# IR_7arry.net
KiCad netlist of a schematic drawn in Altium Designer
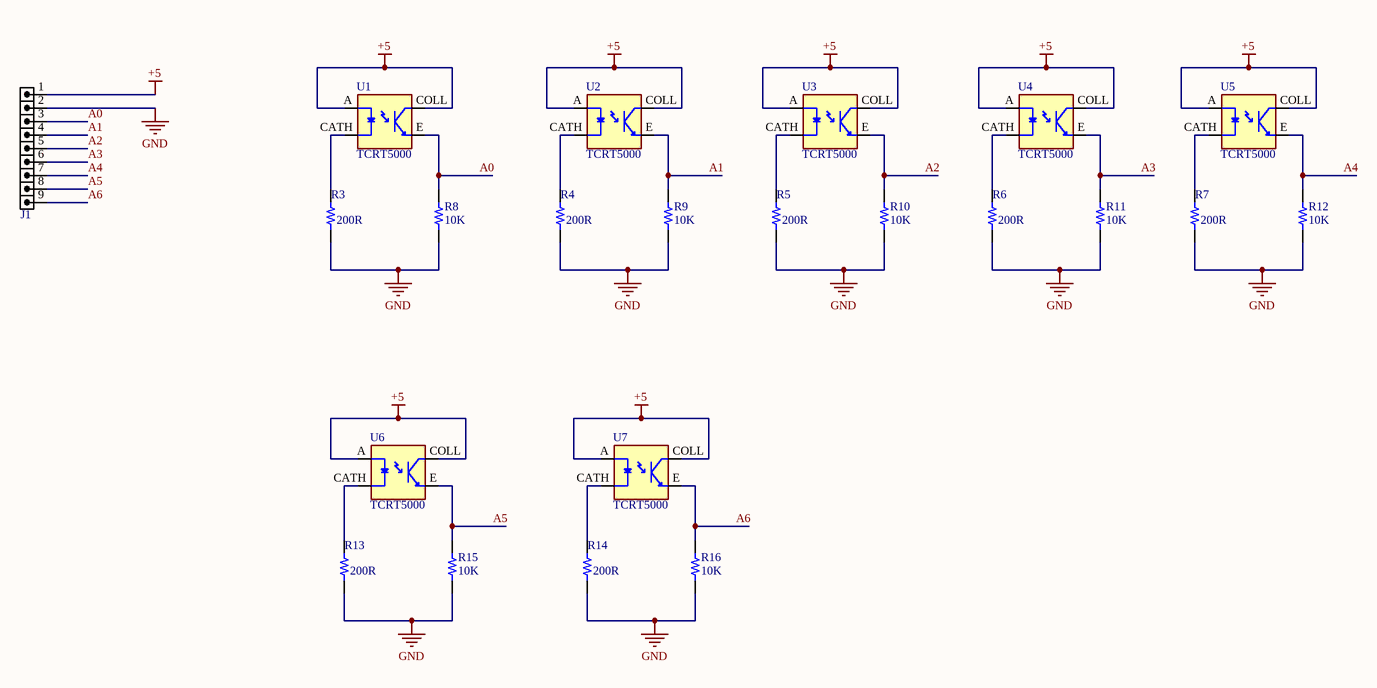
[diagram p0: IR_7arry.SchDoc]

(export (version "E")
  (design (tool "Eeschema 10.0.6"))
  (components
    (comp (ref "J1")
      (value "HDR1X9")
      (footprint "HDRR_M_1X9")
      (description "CONN, HEADER, RightAngle, Male, pitch: 2.54mm, 9POS")
      (libsource (lib "Conn Header") (part "HDRR_M_1X9"))
    )
    (comp (ref "R3")
      (value "200R")
      (footprint "RES TH 1/8W AXIAL-0.25")
      (description "TH Resistor")
      (libsource (lib "Resistor") (part "Res TH 1/8W AXIAL-0.25"))
    )
    (comp (ref "R4")
      (value "200R")
      (footprint "RES TH 1/8W AXIAL-0.25")
      (description "TH Resistor")
      (libsource (lib "Resistor") (part "Res TH 1/8W AXIAL-0.25"))
    )
    (comp (ref "R5")
      (value "200R")
      (footprint "RES TH 1/8W AXIAL-0.25")
      (description "TH Resistor")
      (libsource (lib "Resistor") (part "Res TH 1/8W AXIAL-0.25"))
    )
    (comp (ref "R6")
      (value "200R")
      (footprint "RES TH 1/8W AXIAL-0.25")
      (description "TH Resistor")
      (libsource (lib "Resistor") (part "Res TH 1/8W AXIAL-0.25"))
    )
    (comp (ref "R7")
      (value "200R")
      (footprint "RES TH 1/8W AXIAL-0.25")
      (description "TH Resistor")
      (libsource (lib "Resistor") (part "Res TH 1/8W AXIAL-0.25"))
    )
    (comp (ref "R8")
      (value "10K")
      (footprint "RES TH 1/8W AXIAL-0.25")
      (description "TH Resistor")
      (libsource (lib "Resistor") (part "Res TH 1/8W AXIAL-0.25"))
    )
    (comp (ref "R9")
      (value "10K")
      (footprint "RES TH 1/8W AXIAL-0.25")
      (description "TH Resistor")
      (libsource (lib "Resistor") (part "Res TH 1/8W AXIAL-0.25"))
    )
    (comp (ref "R10")
      (value "10K")
      (footprint "RES TH 1/8W AXIAL-0.25")
      (description "TH Resistor")
      (libsource (lib "Resistor") (part "Res TH 1/8W AXIAL-0.25"))
    )
    (comp (ref "R11")
      (value "10K")
      (footprint "RES TH 1/8W AXIAL-0.25")
      (description "TH Resistor")
      (libsource (lib "Resistor") (part "Res TH 1/8W AXIAL-0.25"))
    )
    (comp (ref "R12")
      (value "10K")
      (footprint "RES TH 1/8W AXIAL-0.25")
      (description "TH Resistor")
      (libsource (lib "Resistor") (part "Res TH 1/8W AXIAL-0.25"))
    )
    (comp (ref "R13")
      (value "200R")
      (footprint "RES TH 1/8W AXIAL-0.25")
      (description "TH Resistor")
      (libsource (lib "Resistor") (part "Res TH 1/8W AXIAL-0.25"))
    )
    (comp (ref "R14")
      (value "200R")
      (footprint "RES TH 1/8W AXIAL-0.25")
      (description "TH Resistor")
      (libsource (lib "Resistor") (part "Res TH 1/8W AXIAL-0.25"))
    )
    (comp (ref "R15")
      (value "10K")
      (footprint "RES TH 1/8W AXIAL-0.25")
      (description "TH Resistor")
      (libsource (lib "Resistor") (part "Res TH 1/8W AXIAL-0.25"))
    )
    (comp (ref "R16")
      (value "10K")
      (footprint "RES TH 1/8W AXIAL-0.25")
      (description "TH Resistor")
      (libsource (lib "Resistor") (part "Res TH 1/8W AXIAL-0.25"))
    )
    (comp (ref "U1")
      (value "TCRT5000")
      (footprint "OPTO_TCRT5000")
      (description "950 nm 60 mA Through Hole Reflective Optical Sensor with Transistor Output")
      (libsource (lib "TCRT5000") (part "TCRT5000"))
    )
    (comp (ref "U2")
      (value "TCRT5000")
      (footprint "OPTO_TCRT5000")
      (description "950 nm 60 mA Through Hole Reflective Optical Sensor with Transistor Output")
      (libsource (lib "TCRT5000") (part "TCRT5000"))
    )
    (comp (ref "U3")
      (value "TCRT5000")
      (footprint "OPTO_TCRT5000")
      (description "950 nm 60 mA Through Hole Reflective Optical Sensor with Transistor Output")
      (libsource (lib "TCRT5000") (part "TCRT5000"))
    )
    (comp (ref "U4")
      (value "TCRT5000")
      (footprint "OPTO_TCRT5000")
      (description "950 nm 60 mA Through Hole Reflective Optical Sensor with Transistor Output")
      (libsource (lib "TCRT5000") (part "TCRT5000"))
    )
    (comp (ref "U5")
      (value "TCRT5000")
      (footprint "OPTO_TCRT5000")
      (description "950 nm 60 mA Through Hole Reflective Optical Sensor with Transistor Output")
      (libsource (lib "TCRT5000") (part "TCRT5000"))
    )
    (comp (ref "U6")
      (value "TCRT5000")
      (footprint "OPTO_TCRT5000")
      (description "950 nm 60 mA Through Hole Reflective Optical Sensor with Transistor Output")
      (libsource (lib "TCRT5000") (part "TCRT5000"))
    )
    (comp (ref "U7")
      (value "TCRT5000")
      (footprint "OPTO_TCRT5000")
      (description "950 nm 60 mA Through Hole Reflective Optical Sensor with Transistor Output")
      (libsource (lib "TCRT5000") (part "TCRT5000"))
    )
  )
  (nets
    (net (code "1") (name "+5") (class "Default")
      (node (ref "J1") (pin "1") (pinfunction "1_1") (pintype "passive"))
      (node (ref "U1") (pin "A") (pinfunction "A_A") (pintype "passive"))
      (node (ref "U1") (pin "COLL") (pinfunction "COLL_COLL") (pintype "passive"))
      (node (ref "U2") (pin "A") (pinfunction "A_A") (pintype "passive"))
      (node (ref "U2") (pin "COLL") (pinfunction "COLL_COLL") (pintype "passive"))
      (node (ref "U3") (pin "A") (pinfunction "A_A") (pintype "passive"))
      (node (ref "U3") (pin "COLL") (pinfunction "COLL_COLL") (pintype "passive"))
      (node (ref "U4") (pin "A") (pinfunction "A_A") (pintype "passive"))
      (node (ref "U4") (pin "COLL") (pinfunction "COLL_COLL") (pintype "passive"))
      (node (ref "U5") (pin "A") (pinfunction "A_A") (pintype "passive"))
      (node (ref "U5") (pin "COLL") (pinfunction "COLL_COLL") (pintype "passive"))
      (node (ref "U6") (pin "A") (pinfunction "A_A") (pintype "passive"))
      (node (ref "U6") (pin "COLL") (pinfunction "COLL_COLL") (pintype "passive"))
      (node (ref "U7") (pin "A") (pinfunction "A_A") (pintype "passive"))
      (node (ref "U7") (pin "COLL") (pinfunction "COLL_COLL") (pintype "passive"))
    )
    (net (code "2") (name "/A0") (class "Default")
      (node (ref "J1") (pin "3") (pinfunction "3_3") (pintype "passive"))
      (node (ref "R8") (pin "2") (pinfunction "2_2") (pintype "passive"))
      (node (ref "U1") (pin "E") (pinfunction "E_E") (pintype "passive"))
    )
    (net (code "3") (name "/A1") (class "Default")
      (node (ref "J1") (pin "4") (pinfunction "4_4") (pintype "passive"))
      (node (ref "R9") (pin "2") (pinfunction "2_2") (pintype "passive"))
      (node (ref "U2") (pin "E") (pinfunction "E_E") (pintype "passive"))
    )
    (net (code "4") (name "/A2") (class "Default")
      (node (ref "J1") (pin "5") (pinfunction "5_5") (pintype "passive"))
      (node (ref "R10") (pin "2") (pinfunction "2_2") (pintype "passive"))
      (node (ref "U3") (pin "E") (pinfunction "E_E") (pintype "passive"))
    )
    (net (code "5") (name "/A3") (class "Default")
      (node (ref "J1") (pin "6") (pinfunction "6_6") (pintype "passive"))
      (node (ref "R11") (pin "2") (pinfunction "2_2") (pintype "passive"))
      (node (ref "U4") (pin "E") (pinfunction "E_E") (pintype "passive"))
    )
    (net (code "6") (name "/A4") (class "Default")
      (node (ref "J1") (pin "7") (pinfunction "7_7") (pintype "passive"))
      (node (ref "R12") (pin "2") (pinfunction "2_2") (pintype "passive"))
      (node (ref "U5") (pin "E") (pinfunction "E_E") (pintype "passive"))
    )
    (net (code "7") (name "/A5") (class "Default")
      (node (ref "J1") (pin "8") (pinfunction "8_8") (pintype "passive"))
      (node (ref "R15") (pin "2") (pinfunction "2_2") (pintype "passive"))
      (node (ref "U6") (pin "E") (pinfunction "E_E") (pintype "passive"))
    )
    (net (code "8") (name "/A6") (class "Default")
      (node (ref "J1") (pin "9") (pinfunction "9_9") (pintype "passive"))
      (node (ref "R16") (pin "2") (pinfunction "2_2") (pintype "passive"))
      (node (ref "U7") (pin "E") (pinfunction "E_E") (pintype "passive"))
    )
    (net (code "9") (name "GND") (class "Default")
      (node (ref "J1") (pin "2") (pinfunction "2_2") (pintype "passive"))
      (node (ref "R10") (pin "1") (pinfunction "1_1") (pintype "passive"))
      (node (ref "R11") (pin "1") (pinfunction "1_1") (pintype "passive"))
      (node (ref "R12") (pin "1") (pinfunction "1_1") (pintype "passive"))
      (node (ref "R13") (pin "1") (pinfunction "1_1") (pintype "passive"))
      (node (ref "R14") (pin "1") (pinfunction "1_1") (pintype "passive"))
      (node (ref "R15") (pin "1") (pinfunction "1_1") (pintype "passive"))
      (node (ref "R16") (pin "1") (pinfunction "1_1") (pintype "passive"))
      (node (ref "R3") (pin "1") (pinfunction "1_1") (pintype "passive"))
      (node (ref "R4") (pin "1") (pinfunction "1_1") (pintype "passive"))
      (node (ref "R5") (pin "1") (pinfunction "1_1") (pintype "passive"))
      (node (ref "R6") (pin "1") (pinfunction "1_1") (pintype "passive"))
      (node (ref "R7") (pin "1") (pinfunction "1_1") (pintype "passive"))
      (node (ref "R8") (pin "1") (pinfunction "1_1") (pintype "passive"))
      (node (ref "R9") (pin "1") (pinfunction "1_1") (pintype "passive"))
    )
    (net (code "10") (name "Net-(R3-Pad2)") (class "Default")
      (node (ref "R3") (pin "2") (pinfunction "2_2") (pintype "passive"))
      (node (ref "U1") (pin "CATH") (pinfunction "CATH_CATH") (pintype "passive"))
    )
    (net (code "11") (name "Net-(R4-Pad2)") (class "Default")
      (node (ref "R4") (pin "2") (pinfunction "2_2") (pintype "passive"))
      (node (ref "U2") (pin "CATH") (pinfunction "CATH_CATH") (pintype "passive"))
    )
    (net (code "12") (name "Net-(R5-Pad2)") (class "Default")
      (node (ref "R5") (pin "2") (pinfunction "2_2") (pintype "passive"))
      (node (ref "U3") (pin "CATH") (pinfunction "CATH_CATH") (pintype "passive"))
    )
    (net (code "13") (name "Net-(R6-Pad2)") (class "Default")
      (node (ref "R6") (pin "2") (pinfunction "2_2") (pintype "passive"))
      (node (ref "U4") (pin "CATH") (pinfunction "CATH_CATH") (pintype "passive"))
    )
    (net (code "14") (name "Net-(R7-Pad2)") (class "Default")
      (node (ref "R7") (pin "2") (pinfunction "2_2") (pintype "passive"))
      (node (ref "U5") (pin "CATH") (pinfunction "CATH_CATH") (pintype "passive"))
    )
    (net (code "15") (name "Net-(R13-Pad2)") (class "Default")
      (node (ref "R13") (pin "2") (pinfunction "2_2") (pintype "passive"))
      (node (ref "U6") (pin "CATH") (pinfunction "CATH_CATH") (pintype "passive"))
    )
    (net (code "16") (name "Net-(R14-Pad2)") (class "Default")
      (node (ref "R14") (pin "2") (pinfunction "2_2") (pintype "passive"))
      (node (ref "U7") (pin "CATH") (pinfunction "CATH_CATH") (pintype "passive"))
    )
  )
)
